# Power.net
KiCad netlist of a schematic drawn in Altium Designer
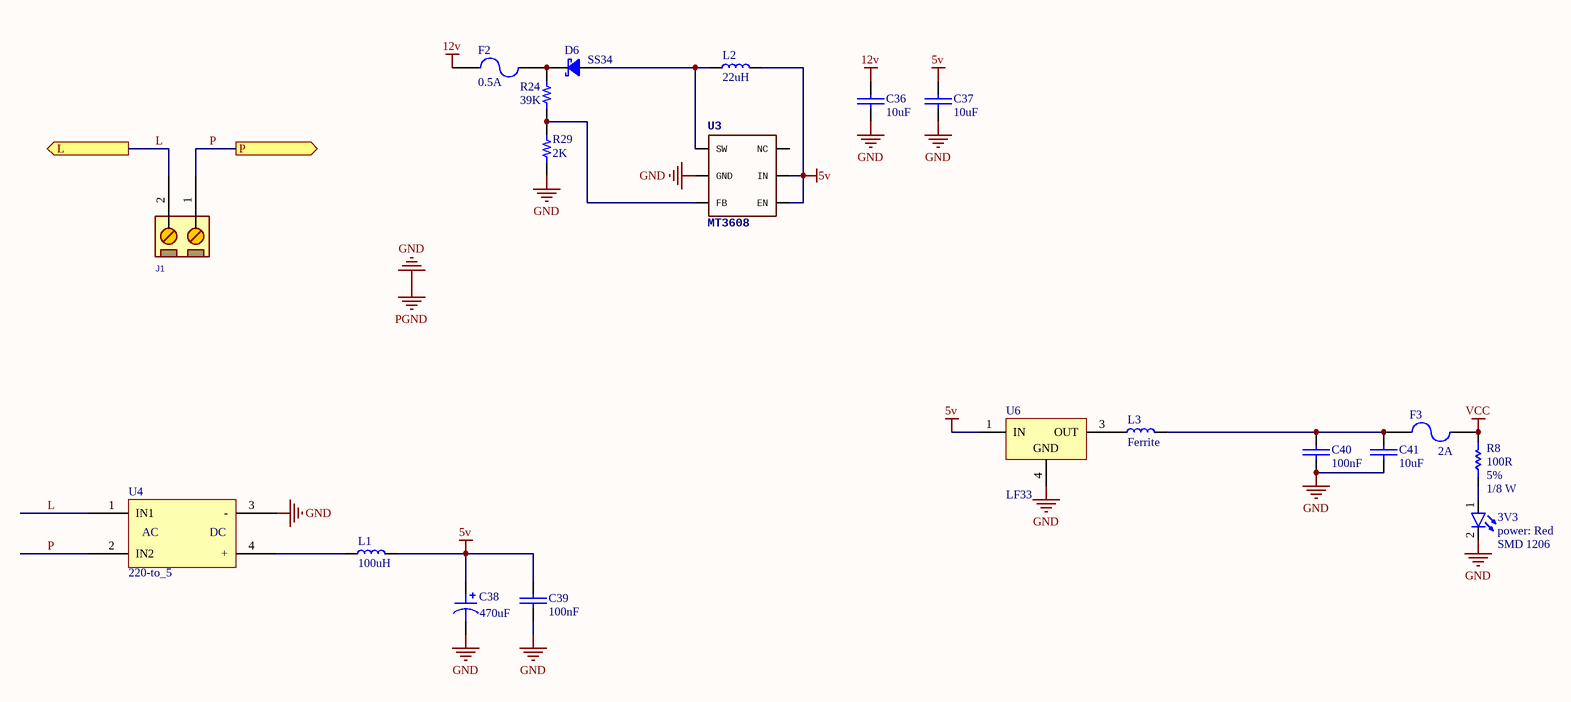
[diagram p0: Power.SchDoc]

(export (version "E")
  (design (tool "Eeschema 10.0.6"))
  (components
    (comp (ref "3V3")
      (value "~")
      (footprint "LED_1206_RED")
      (description "LED")
      (fields
        (field (name "POWER") "Red")
        (field (name "SIZE") "SMD 1206")
        (field (name "DESIGNER") "Saeid Jorablo")
      )
      (libsource (lib "My_Library") (part "LED"))
    )
    (comp (ref "C36")
      (value "10uF")
      (footprint "CAP 0603_1608")
      (description "Bipolar Capacitor")
      (fields (field (name "VOLTAGE") "100V") (field (name "DESIGNER") "Saeid Jorablo"))
      (libsource (lib "My_Library") (part "Cap-Bipolar"))
    )
    (comp (ref "C37")
      (value "10uF")
      (footprint "CAP 0603_1608")
      (description "Bipolar Capacitor")
      (fields (field (name "VOLTAGE") "100V") (field (name "DESIGNER") "Saeid Jorablo"))
      (libsource (lib "My_Library") (part "Cap-Bipolar"))
    )
    (comp (ref "C38")
      (value "470uF")
      (footprint "CAP TAN SMD 7343")
      (description "SMT TAN Polarised Capacitor")
      (libsource (lib "CAPACITOR") (part "Pol Cap SMD TAN 7343 SIZE D"))
    )
    (comp (ref "C39")
      (value "100nF")
      (footprint "CAP 0603_1608")
      (description "Bipolar Capacitor")
      (fields (field (name "VOLTAGE") "100V") (field (name "DESIGNER") "Saeid Jorablo"))
      (libsource (lib "My_Library") (part "Cap-Bipolar"))
    )
    (comp (ref "C40")
      (value "100nF")
      (footprint "CAP 0805_2012")
      (description "Bipolar Capacitor")
      (fields (field (name "VOLTAGE") "100V") (field (name "DESIGNER") "Saeid Jorablo"))
      (libsource (lib "My_Library") (part "Cap-Bipolar"))
    )
    (comp (ref "C41")
      (value "10uF")
      (footprint "CAP 0805_2012")
      (description "Bipolar Capacitor")
      (fields (field (name "VOLTAGE") "100V") (field (name "DESIGNER") "Saeid Jorablo"))
      (libsource (lib "My_Library") (part "Cap-Bipolar"))
    )
    (comp (ref "D6")
      (value "SS34")
      (footprint "DO-214AC SMA")
      (description "Diode Schottky 40V 3A Through Hole DO-201AD")
      (fields (field (name "PARTNUMBER") "1N5822-E3/54"))
      (libsource (lib "Diode") (part "1N5822 (THD)"))
    )
    (comp (ref "F2")
      (value "0.5A")
      (footprint "FUSE_1206")
      (fields (field (name "Comment") "Fuse 0805"))
      (libsource (lib "FUSE_FERRITE_VDR") (part "Fuse 0805"))
    )
    (comp (ref "F3")
      (value "2A")
      (footprint "FUSE_1206")
      (fields (field (name "Comment") "Fuse 1206"))
      (libsource (lib "FUSE_FERRITE_VDR") (part "Fuse 1206"))
    )
    (comp (ref "J1")
      (value "CONN_TB2")
      (footprint "P_TBB_2")
      (description "CONN, TERMINAL BLOCK, 5.08mm pitch")
      (libsource (lib "TERMINAL") (part "TB2 BLUE"))
    )
    (comp (ref "L1")
      (value "100uH")
      (footprint "IND 10X11MM")
      (description "SMT Inductor")
      (fields (field (name "Comment") "Inductor SMD POWER 10X11mm"))
      (libsource (lib "INDUCTOR") (part "Inductor SMD POWER 10X11mm"))
    )
    (comp (ref "L2")
      (value "22uH")
      (footprint "IND 5X5MM")
      (description "SMT Inductor")
      (fields (field (name "Comment") "Inductor SMD POWER 10X11mm"))
      (libsource (lib "INDUCTOR") (part "Inductor SMD POWER 10X11mm"))
    )
    (comp (ref "L3")
      (value "Ferrite")
      (footprint "IND 1206_3216")
      (description "SMT Inductor")
      (libsource (lib "Inductor") (part "Ind 1206"))
    )
    (comp (ref "R8")
      (value "100R")
      (footprint "RES 0805_2012")
      (description "Resistor")
      (fields (field (name "TOLERANCE") "5%") (field (name "POWER") "1/8 W"))
      (libsource (lib "My_Library") (part "Resistor"))
    )
    (comp (ref "R24")
      (value "39K")
      (footprint "RES 0805_2012")
      (description "SMT Resistor")
      (libsource (lib "Resistor") (part "Res 0805"))
    )
    (comp (ref "R29")
      (value "2K")
      (footprint "RES 0805_2012")
      (description "SMT Resistor")
      (libsource (lib "Resistor") (part "Res 0805"))
    )
    (comp (ref "U3")
      (value "MT3608")
      (footprint "SOT-23-6 2.9X2.8MM P0.95MM")
      (description "Boost chip")
      (libsource (lib "Chip") (part "MT3608 (SMD)"))
    )
    (comp (ref "U4")
      (value "220-to_5")
      (footprint "HLK_5W")
      (description "Isolated 3W Power Module")
      (libsource (lib "MY_LIB") (part "H-Link"))
    )
    (comp (ref "U6")
      (value "LF33")
      (footprint "TO252")
      (description "500mA, Very Low Drop (0.45V) Voltage Regulator, 3.3V, 3-Pin DPAK, Tape and Reel")
      (fields (field (name "PARTNUMBER") "LF33CDT-TR"))
      (libsource (lib "Chip") (part "LF33 (SMD)"))
    )
  )
  (nets
    (net (code "1") (name "/L") (class "Default")
      (node (ref "J1") (pin "2") (pinfunction "2_2") (pintype "passive"))
      (node (ref "U4") (pin "1") (pinfunction "IN1_1") (pintype "passive"))
    )
    (net (code "2") (name "/P") (class "Default")
      (node (ref "J1") (pin "1") (pinfunction "1_1") (pintype "passive"))
      (node (ref "U4") (pin "2") (pinfunction "IN2_2") (pintype "passive"))
    )
    (net (code "3") (name "5v") (class "Default")
      (node (ref "C37") (pin "2") (pinfunction "-_2") (pintype "passive"))
      (node (ref "C38") (pin "1") (pinfunction "1_1") (pintype "passive"))
      (node (ref "C39") (pin "2") (pinfunction "-_2") (pintype "passive"))
      (node (ref "L1") (pin "2") (pinfunction "2_2") (pintype "passive"))
      (node (ref "L2") (pin "2") (pinfunction "2_2") (pintype "passive"))
      (node (ref "U3") (pin "4") (pinfunction "EN_4") (pintype "passive"))
      (node (ref "U3") (pin "5") (pinfunction "IN_5") (pintype "passive"))
      (node (ref "U6") (pin "1") (pinfunction "IN_1") (pintype "power_in"))
    )
    (net (code "4") (name "12v") (class "Default")
      (node (ref "C36") (pin "2") (pinfunction "-_2") (pintype "passive"))
      (node (ref "F2") (pin "1") (pinfunction "1_1") (pintype "passive"))
    )
    (net (code "5") (name "GND") (class "Default")
      (node (ref "3V3") (pin "2") (pinfunction "K_2") (pintype "passive"))
      (node (ref "C36") (pin "1") (pinfunction "+_1") (pintype "passive"))
      (node (ref "C37") (pin "1") (pinfunction "+_1") (pintype "passive"))
      (node (ref "C38") (pin "2") (pinfunction "2_2") (pintype "passive"))
      (node (ref "C39") (pin "1") (pinfunction "+_1") (pintype "passive"))
      (node (ref "C40") (pin "2") (pinfunction "-_2") (pintype "passive"))
      (node (ref "C41") (pin "2") (pinfunction "-_2") (pintype "passive"))
      (node (ref "R29") (pin "1") (pinfunction "1_1") (pintype "passive"))
      (node (ref "U3") (pin "2") (pinfunction "GND_2") (pintype "passive"))
      (node (ref "U4") (pin "3") (pinfunction "-_3") (pintype "passive"))
      (node (ref "U6") (pin "4") (pinfunction "GND_4") (pintype "power_in"))
    )
    (net (code "6") (name "Net-(3V3-A)") (class "Default")
      (node (ref "3V3") (pin "1") (pinfunction "A_1") (pintype "passive"))
      (node (ref "R8") (pin "1") (pinfunction "1_1") (pintype "passive"))
    )
    (net (code "7") (name "Net-(C40-+)") (class "Default")
      (node (ref "C40") (pin "1") (pinfunction "+_1") (pintype "passive"))
      (node (ref "C41") (pin "1") (pinfunction "+_1") (pintype "passive"))
      (node (ref "F3") (pin "1") (pinfunction "1_1") (pintype "passive"))
      (node (ref "L3") (pin "2") (pinfunction "2_2") (pintype "passive"))
    )
    (net (code "8") (name "Net-(D6-Pad2)") (class "Default")
      (node (ref "D6") (pin "2") (pinfunction "2_2") (pintype "passive"))
      (node (ref "F2") (pin "2") (pinfunction "2_2") (pintype "passive"))
      (node (ref "R24") (pin "2") (pinfunction "2_2") (pintype "passive"))
    )
    (net (code "9") (name "Net-(U3-FB)") (class "Default")
      (node (ref "R24") (pin "1") (pinfunction "1_1") (pintype "passive"))
      (node (ref "R29") (pin "2") (pinfunction "2_2") (pintype "passive"))
      (node (ref "U3") (pin "3") (pinfunction "FB_3") (pintype "passive"))
    )
    (net (code "10") (name "Net-(U3-SW)") (class "Default")
      (node (ref "D6") (pin "1") (pinfunction "1_1") (pintype "passive"))
      (node (ref "L2") (pin "1") (pinfunction "1_1") (pintype "passive"))
      (node (ref "U3") (pin "1") (pinfunction "SW_1") (pintype "passive"))
    )
    (net (code "11") (name "Net-(U4-+)") (class "Default")
      (node (ref "L1") (pin "1") (pinfunction "1_1") (pintype "passive"))
      (node (ref "U4") (pin "4") (pinfunction "+_4") (pintype "passive"))
    )
    (net (code "12") (name "Net-(U6-OUT)") (class "Default")
      (node (ref "L3") (pin "1") (pinfunction "1_1") (pintype "passive"))
      (node (ref "U6") (pin "3") (pinfunction "OUT_3") (pintype "power_in"))
    )
    (net (code "13") (name "VCC") (class "Default")
      (node (ref "F3") (pin "2") (pinfunction "2_2") (pintype "passive"))
      (node (ref "R8") (pin "2") (pinfunction "2_2") (pintype "passive"))
    )
    (net (code "14") (name "unconnected-(U3-NC-Pad6)") (class "Default")
      (node (ref "U3") (pin "6") (pinfunction "NC_6") (pintype "passive"))
    )
  )
)
